# ftdi.net
KiCad netlist of a schematic drawn in EAGLE
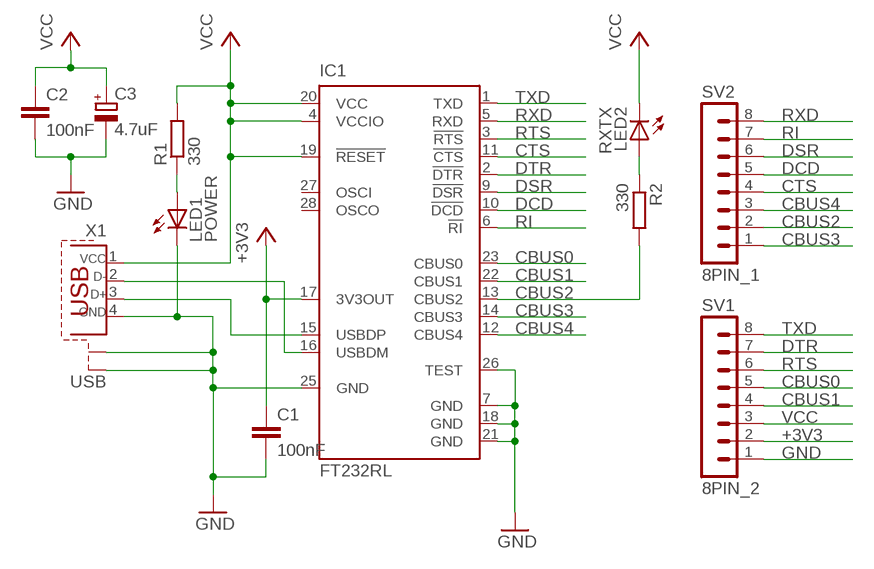
[diagram p0: schematic, sheet 1]

(export (version "E")
  (design (tool "Eeschema 10.0.6"))
  (components
    (comp (ref "C1")
      (value "100nF")
      (footprint "eagle-import:C050-024X044")
      (libsource (lib "eagle-import") (part "C-EU050-024X044"))
    )
    (comp (ref "C2")
      (value "100nF")
      (footprint "eagle-import:C050-024X044")
      (libsource (lib "eagle-import") (part "C-EU050-024X044"))
    )
    (comp (ref "C3")
      (value "4.7uF")
      (footprint "eagle-import:E5-4")
      (libsource (lib "eagle-import") (part "CPOL-EUE5-4"))
    )
    (comp (ref "IC1")
      (value "FT232RL")
      (footprint "eagle-import:SSOP28")
      (libsource (lib "eagle-import") (part "FT232RL"))
    )
    (comp (ref "LED1")
      (value "POWER")
      (footprint "eagle-import:LED3MM")
      (libsource (lib "eagle-import") (part "LED3MM"))
    )
    (comp (ref "LED2")
      (value "RXTX")
      (footprint "eagle-import:LED3MM")
      (libsource (lib "eagle-import") (part "LED3MM"))
    )
    (comp (ref "R1")
      (value "330")
      (footprint "eagle-import:0204_7")
      (libsource (lib "eagle-import") (part "R-EU_0204/7"))
    )
    (comp (ref "R2")
      (value "330")
      (footprint "eagle-import:0204_7")
      (libsource (lib "eagle-import") (part "R-EU_0204/7"))
    )
    (comp (ref "SV1")
      (value "8PIN_2")
      (footprint "eagle-import:MA08-1")
      (libsource (lib "eagle-import") (part "MA08-1"))
    )
    (comp (ref "SV2")
      (value "8PIN_1")
      (footprint "eagle-import:MA08-1")
      (libsource (lib "eagle-import") (part "MA08-1"))
    )
    (comp (ref "X1")
      (value "USB")
      (footprint "eagle-import:PN61729-S")
      (libsource (lib "eagle-import") (part "PN61729-S"))
    )
  )
  (nets
    (net (code "1") (name "+3V3") (class "Default")
      (node (ref "C1") (pin "1") (pinfunction "1_1") (pintype "passive"))
      (node (ref "IC1") (pin "17") (pinfunction "3V3OUT_17") (pintype "output"))
      (node (ref "SV1") (pin "2") (pinfunction "2_2") (pintype "passive"))
    )
    (net (code "2") (name "/CBUS0") (class "Default")
      (node (ref "IC1") (pin "23") (pinfunction "CBUS0_23") (pintype "bidirectional"))
      (node (ref "SV1") (pin "5") (pinfunction "5_5") (pintype "passive"))
    )
    (net (code "3") (name "/CBUS1") (class "Default")
      (node (ref "IC1") (pin "22") (pinfunction "CBUS1_22") (pintype "bidirectional"))
      (node (ref "SV1") (pin "4") (pinfunction "4_4") (pintype "passive"))
    )
    (net (code "4") (name "/CBUS2") (class "Default")
      (node (ref "IC1") (pin "13") (pinfunction "CBUS2_13") (pintype "bidirectional"))
      (node (ref "R2") (pin "2") (pinfunction "2_2") (pintype "passive"))
      (node (ref "SV2") (pin "2") (pinfunction "2_2") (pintype "passive"))
    )
    (net (code "5") (name "/CBUS3") (class "Default")
      (node (ref "IC1") (pin "14") (pinfunction "CBUS3_14") (pintype "bidirectional"))
      (node (ref "SV2") (pin "1") (pinfunction "1_1") (pintype "passive"))
    )
    (net (code "6") (name "/CBUS4") (class "Default")
      (node (ref "IC1") (pin "12") (pinfunction "CBUS4_12") (pintype "bidirectional"))
      (node (ref "SV2") (pin "3") (pinfunction "3_3") (pintype "passive"))
    )
    (net (code "7") (name "/CTS") (class "Default")
      (node (ref "IC1") (pin "11") (pinfunction "~{CTS}_11") (pintype "input"))
      (node (ref "SV2") (pin "4") (pinfunction "4_4") (pintype "passive"))
    )
    (net (code "8") (name "/DCD") (class "Default")
      (node (ref "IC1") (pin "10") (pinfunction "~{DCD}_10") (pintype "input"))
      (node (ref "SV2") (pin "5") (pinfunction "5_5") (pintype "passive"))
    )
    (net (code "9") (name "/DSR") (class "Default")
      (node (ref "IC1") (pin "9") (pinfunction "~{DSR}_9") (pintype "input"))
      (node (ref "SV2") (pin "6") (pinfunction "6_6") (pintype "passive"))
    )
    (net (code "10") (name "/DTR") (class "Default")
      (node (ref "IC1") (pin "2") (pinfunction "~{DTR}_2") (pintype "output"))
      (node (ref "SV1") (pin "7") (pinfunction "7_7") (pintype "passive"))
    )
    (net (code "11") (name "/RI") (class "Default")
      (node (ref "IC1") (pin "6") (pinfunction "~{RI}_6") (pintype "input"))
      (node (ref "SV2") (pin "7") (pinfunction "7_7") (pintype "passive"))
    )
    (net (code "12") (name "/RTS") (class "Default")
      (node (ref "IC1") (pin "3") (pinfunction "~{RTS}_3") (pintype "output"))
      (node (ref "SV1") (pin "6") (pinfunction "6_6") (pintype "passive"))
    )
    (net (code "13") (name "/RXD") (class "Default")
      (node (ref "IC1") (pin "5") (pinfunction "RXD_5") (pintype "input"))
      (node (ref "SV2") (pin "8") (pinfunction "8_8") (pintype "passive"))
    )
    (net (code "14") (name "/TXD") (class "Default")
      (node (ref "IC1") (pin "1") (pinfunction "TXD_1") (pintype "output"))
      (node (ref "SV1") (pin "8") (pinfunction "8_8") (pintype "passive"))
    )
    (net (code "15") (name "GND") (class "Default")
      (node (ref "C1") (pin "2") (pinfunction "2_2") (pintype "passive"))
      (node (ref "C2") (pin "2") (pinfunction "2_2") (pintype "passive"))
      (node (ref "C3") (pin "-") (pinfunction "-_-") (pintype "passive"))
      (node (ref "IC1") (pin "18") (pinfunction "GND_18") (pintype "power_in"))
      (node (ref "IC1") (pin "21") (pinfunction "GND_21") (pintype "power_in"))
      (node (ref "IC1") (pin "25") (pinfunction "GND_25") (pintype "power_in"))
      (node (ref "IC1") (pin "26") (pinfunction "TEST_26") (pintype "input"))
      (node (ref "IC1") (pin "7") (pinfunction "GND_7") (pintype "power_in"))
      (node (ref "LED1") (pin "K") (pinfunction "C_K") (pintype "passive"))
      (node (ref "SV1") (pin "1") (pinfunction "1_1") (pintype "passive"))
      (node (ref "X1") (pin "4") (pinfunction "4_4") (pintype "passive"))
      (node (ref "X1") (pin "S1") (pinfunction "S1_S1") (pintype "passive"))
      (node (ref "X1") (pin "S2") (pinfunction "S2_S2") (pintype "passive"))
    )
    (net (code "16") (name "Net-(IC1-USBDM)") (class "Default")
      (node (ref "IC1") (pin "16") (pinfunction "USBDM_16") (pintype "bidirectional"))
      (node (ref "X1") (pin "2") (pinfunction "2_2") (pintype "passive"))
    )
    (net (code "17") (name "Net-(IC1-USBDP)") (class "Default")
      (node (ref "IC1") (pin "15") (pinfunction "USBDP_15") (pintype "bidirectional"))
      (node (ref "X1") (pin "3") (pinfunction "3_3") (pintype "passive"))
    )
    (net (code "18") (name "Net-(LED1-PadA)") (class "Default")
      (node (ref "LED1") (pin "A") (pinfunction "A_A") (pintype "passive"))
      (node (ref "R1") (pin "1") (pinfunction "1_1") (pintype "passive"))
    )
    (net (code "19") (name "Net-(LED2-PadA)") (class "Default")
      (node (ref "LED2") (pin "A") (pinfunction "A_A") (pintype "passive"))
      (node (ref "R2") (pin "1") (pinfunction "1_1") (pintype "passive"))
    )
    (net (code "20") (name "VCC") (class "Default")
      (node (ref "C2") (pin "1") (pinfunction "1_1") (pintype "passive"))
      (node (ref "C3") (pin "+") (pinfunction "+_+") (pintype "passive"))
      (node (ref "IC1") (pin "19") (pinfunction "~{RESET}_19") (pintype "input"))
      (node (ref "IC1") (pin "20") (pinfunction "VCC_20") (pintype "power_in"))
      (node (ref "IC1") (pin "4") (pinfunction "VCCIO_4") (pintype "power_in"))
      (node (ref "LED2") (pin "K") (pinfunction "C_K") (pintype "passive"))
      (node (ref "R1") (pin "2") (pinfunction "2_2") (pintype "passive"))
      (node (ref "SV1") (pin "3") (pinfunction "3_3") (pintype "passive"))
      (node (ref "X1") (pin "1") (pinfunction "1_1") (pintype "passive"))
    )
    (net (code "21") (name "unconnected-(IC1-OSCI-Pad27)") (class "Default")
      (node (ref "IC1") (pin "27") (pinfunction "OSCI_27") (pintype "input"))
    )
    (net (code "22") (name "unconnected-(IC1-OSCO-Pad28)") (class "Default")
      (node (ref "IC1") (pin "28") (pinfunction "OSCO_28") (pintype "output"))
    )
  )
)
